# HMC830_PLL.net
KiCad netlist of a schematic drawn in Altium Designer
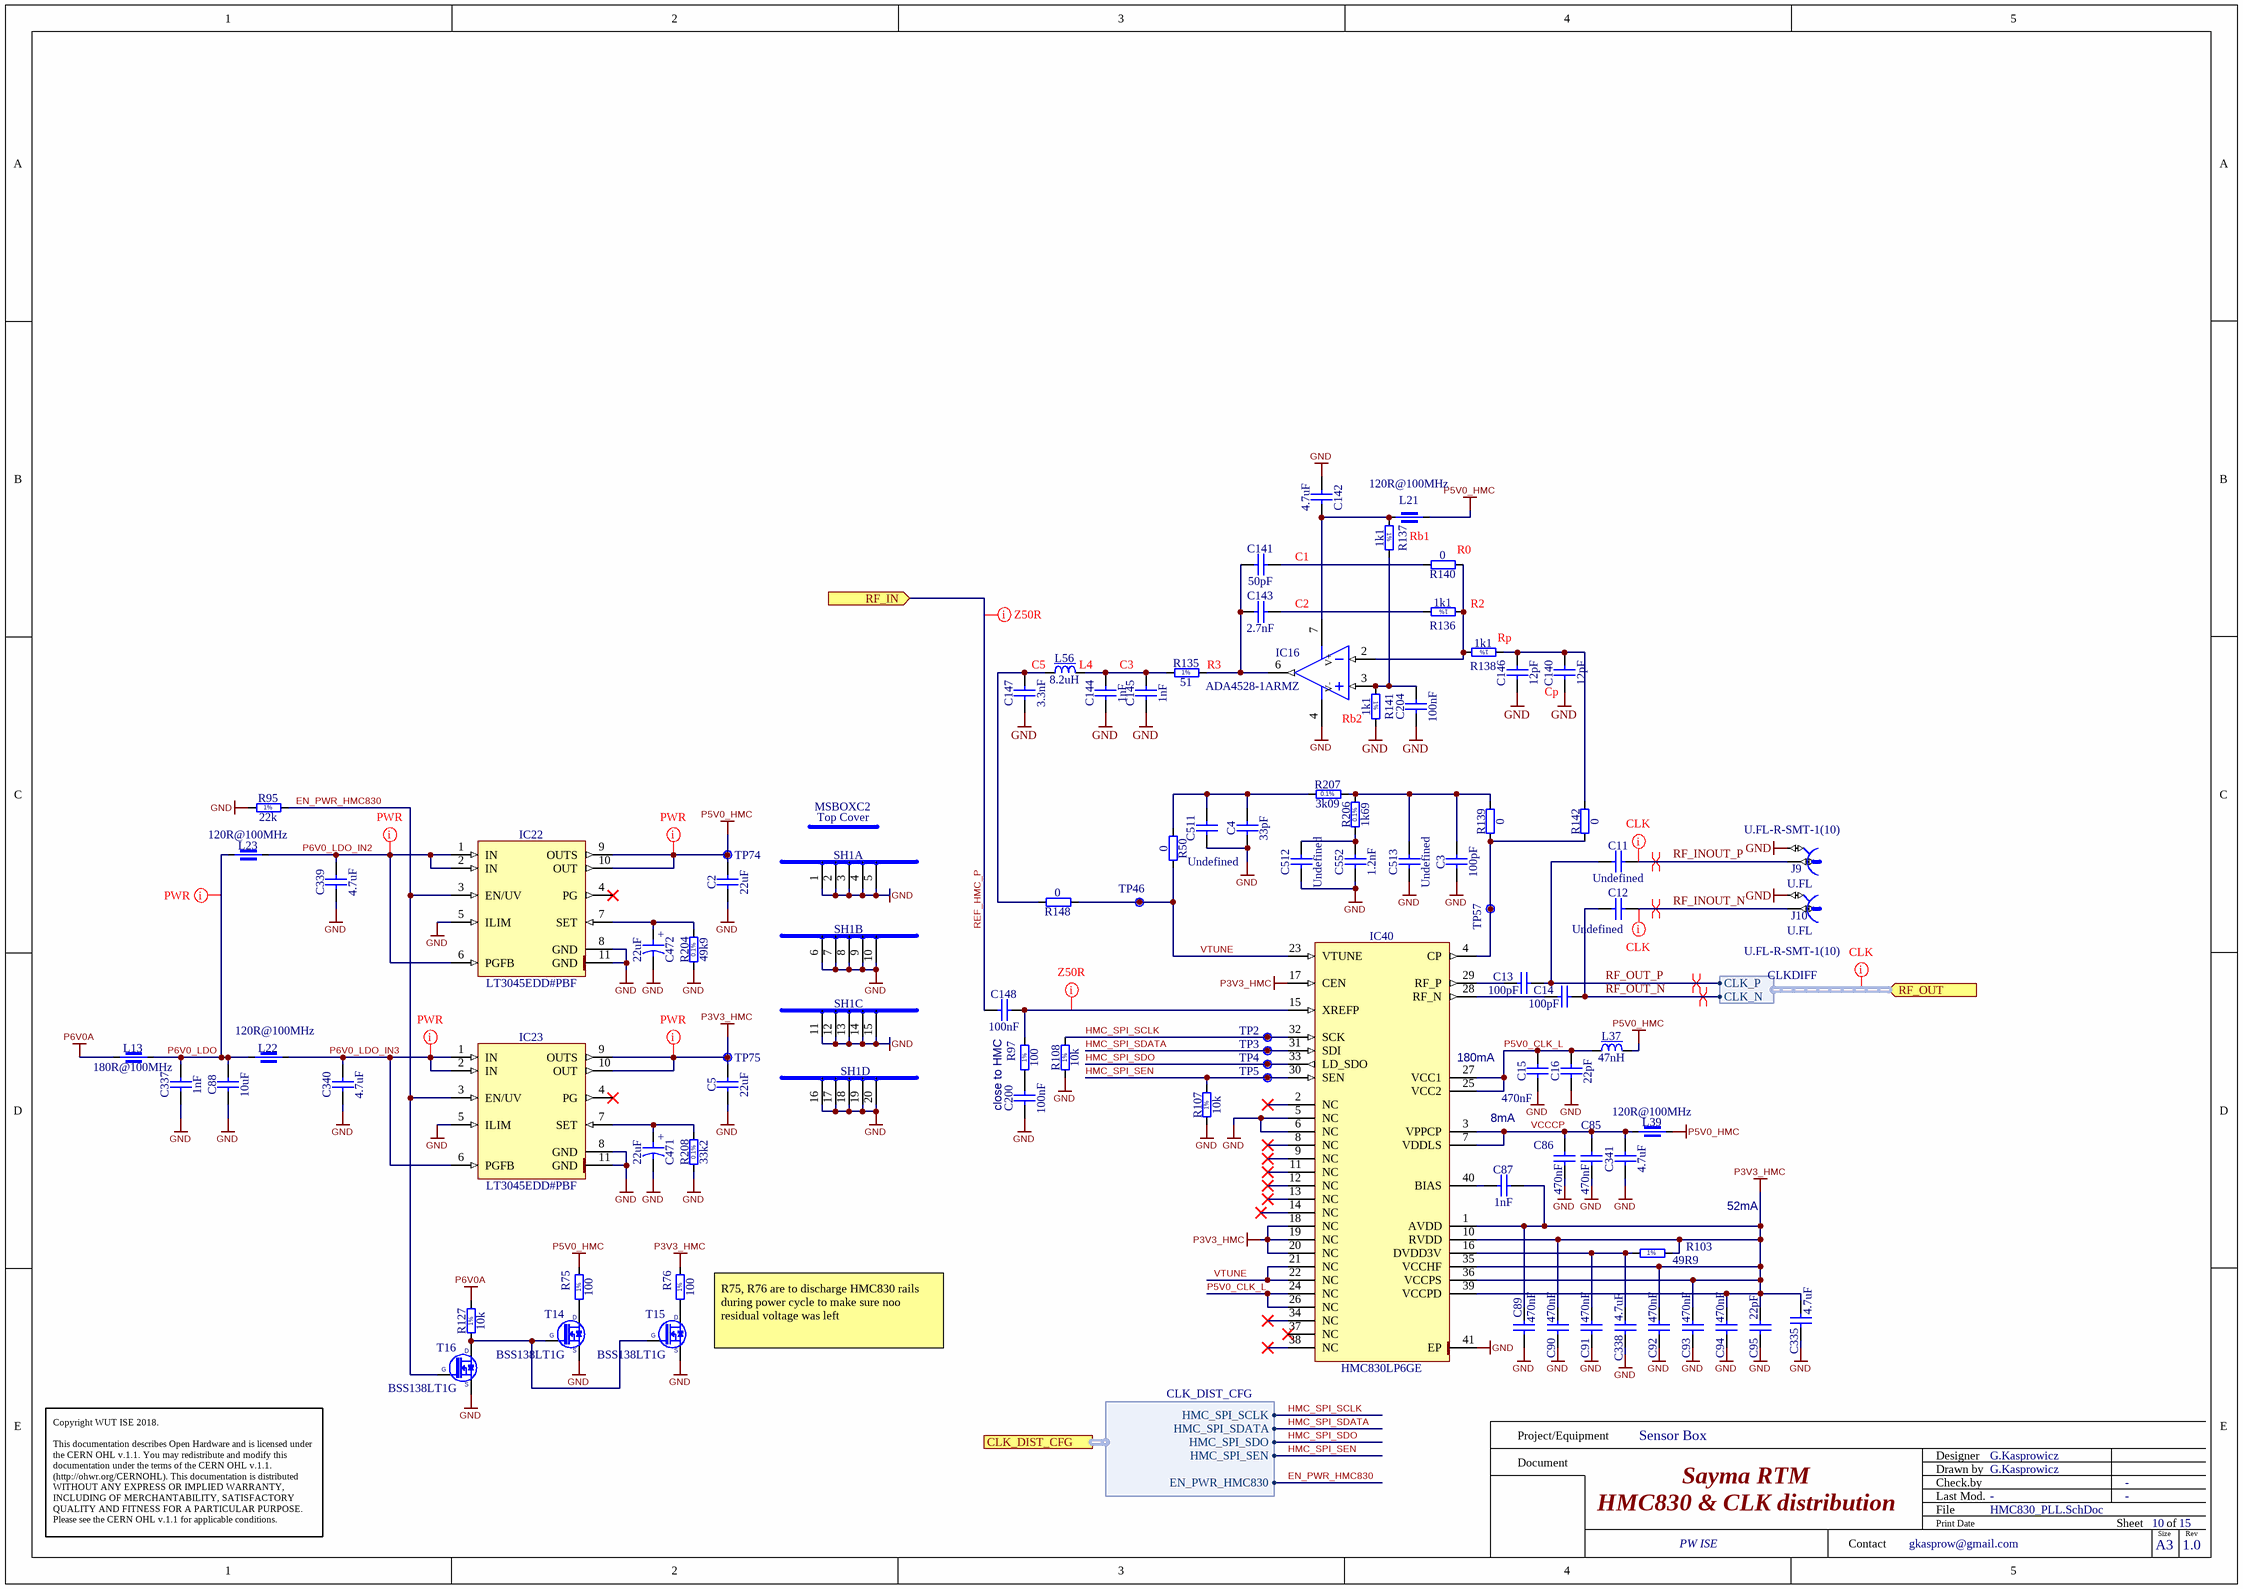
[diagram p0: HMC830_PLL.SchDoc]

(export (version "E")
  (design (tool "Eeschema 10.0.6"))
  (components
    (comp (ref "C2")
      (value "22uF")
      (footprint "CAPC2012X135N")
      (description "Non-polarised capacitor")
      (fields
        (field (name "MANUFACTURER PART NUMBER") "CC0805_22UF_16V_10%_X5R")
        (field (name "MANUFACTURER") "GENERIC")
      )
      (libsource (lib "Capacitors") (part "Capacitor - non polarized"))
    )
    (comp (ref "C3")
      (value "100pF")
      (footprint "CAPC1608X87N")
      (description "Non-polarised capacitor")
      (fields
        (field (name "MANUFACTURER PART NUMBER") "CC0603_100PF_50V_5%_NP0")
        (field (name "MANUFACTURER") "GENERIC")
      )
      (libsource (lib "Capacitors") (part "Capacitor - non polarized"))
    )
    (comp (ref "C4")
      (value "33pF")
      (footprint "CAPC1608X87N")
      (description "Non-polarised capacitor")
      (fields
        (field (name "MANUFACTURER PART NUMBER") "CC0603_33PF_50V_5%_NP0")
        (field (name "MANUFACTURER") "GENERIC")
      )
      (libsource (lib "Capacitors") (part "Capacitor - non polarized"))
    )
    (comp (ref "C5")
      (value "22uF")
      (footprint "CAPC2012X135N")
      (description "Non-polarised capacitor")
      (fields
        (field (name "MANUFACTURER PART NUMBER") "CC0805_22UF_16V_10%_X5R")
        (field (name "MANUFACTURER") "GENERIC")
      )
      (libsource (lib "Capacitors") (part "Capacitor - non polarized"))
    )
    (comp (ref "C11")
      (value "Undefined")
      (footprint "CAPC1005X55N")
      (description "Non-polarised capacitor")
      (fields (field (name "PART NUMBER") "CC0402_NO-VALUE"))
      (libsource (lib "Capacitors") (part "Capacitor - non polarized"))
    )
    (comp (ref "C12")
      (value "Undefined")
      (footprint "CAPC1005X55N")
      (description "Non-polarised capacitor")
      (fields (field (name "PART NUMBER") "CC0402_NO-VALUE"))
      (libsource (lib "Capacitors") (part "Capacitor - non polarized"))
    )
    (comp (ref "C13")
      (value "100pF")
      (footprint "CAPC1608X87N")
      (description "Non-polarised capacitor")
      (fields
        (field (name "MANUFACTURER PART NUMBER") "CC0603_100PF_50V_5%_NP0")
        (field (name "MANUFACTURER") "GENERIC")
      )
      (libsource (lib "Capacitors") (part "Capacitor - non polarized"))
    )
    (comp (ref "C14")
      (value "100pF")
      (footprint "CAPC1608X87N")
      (description "Non-polarised capacitor")
      (fields
        (field (name "MANUFACTURER PART NUMBER") "CC0603_100PF_50V_5%_NP0")
        (field (name "MANUFACTURER") "GENERIC")
      )
      (libsource (lib "Capacitors") (part "Capacitor - non polarized"))
    )
    (comp (ref "C15")
      (value "470nF")
      (footprint "CAPC1005X55N")
      (description "Non-polarised capacitor")
      (fields
        (field (name "MANUFACTURER PART NUMBER") "CC0402_470NF_16V_10%_X5R")
        (field (name "MANUFACTURER") "GENERIC")
      )
      (libsource (lib "Capacitors") (part "Capacitor - non polarized"))
    )
    (comp (ref "C16")
      (value "22pF")
      (footprint "CAPC1005X55N")
      (description "Non-polarised capacitor")
      (fields
        (field (name "MANUFACTURER PART NUMBER") "CC0402_22PF_50V_5%_C0G")
        (field (name "MANUFACTURER") "GENERIC")
      )
      (libsource (lib "Capacitors") (part "Capacitor - non polarized"))
    )
    (comp (ref "C85")
      (value "470nF")
      (footprint "CAPC1005X55N")
      (description "Non-polarised capacitor")
      (fields
        (field (name "MANUFACTURER PART NUMBER") "CC0402_470NF_16V_10%_X5R")
        (field (name "MANUFACTURER") "GENERIC")
      )
      (libsource (lib "Capacitors") (part "Capacitor - non polarized"))
    )
    (comp (ref "C86")
      (value "470nF")
      (footprint "CAPC1005X55N")
      (description "Non-polarised capacitor")
      (fields
        (field (name "MANUFACTURER PART NUMBER") "CC0402_470NF_16V_10%_X5R")
        (field (name "MANUFACTURER") "GENERIC")
      )
      (libsource (lib "Capacitors") (part "Capacitor - non polarized"))
    )
    (comp (ref "C87")
      (value "1nF")
      (footprint "CAPC1005X55N")
      (description "Non-polarised capacitor")
      (fields
        (field (name "MANUFACTURER PART NUMBER") "CC0402_1NF_50V_10%_X7R")
        (field (name "MANUFACTURER") "GENERIC")
      )
      (libsource (lib "Capacitors") (part "Capacitor - non polarized"))
    )
    (comp (ref "C88")
      (value "10uF")
      (footprint "CAPC3216X180N")
      (description "Non-polarised capacitor")
      (fields
        (field (name "MANUFACTURER PART NUMBER") "CC1206_10uF_25V_10%_X7R")
        (field (name "MANUFACTURER") "GENERIC")
      )
      (libsource (lib "Capacitors") (part "Capacitor - non polarized"))
    )
    (comp (ref "C89")
      (value "470nF")
      (footprint "CAPC1005X55N")
      (description "Non-polarised capacitor")
      (fields
        (field (name "MANUFACTURER PART NUMBER") "CC0402_470NF_16V_10%_X5R")
        (field (name "MANUFACTURER") "GENERIC")
      )
      (libsource (lib "Capacitors") (part "Capacitor - non polarized"))
    )
    (comp (ref "C90")
      (value "470nF")
      (footprint "CAPC1005X55N")
      (description "Non-polarised capacitor")
      (fields
        (field (name "MANUFACTURER PART NUMBER") "CC0402_470NF_16V_10%_X5R")
        (field (name "MANUFACTURER") "GENERIC")
      )
      (libsource (lib "Capacitors") (part "Capacitor - non polarized"))
    )
    (comp (ref "C91")
      (value "470nF")
      (footprint "CAPC1005X55N")
      (description "Non-polarised capacitor")
      (fields
        (field (name "MANUFACTURER PART NUMBER") "CC0402_470NF_16V_10%_X5R")
        (field (name "MANUFACTURER") "GENERIC")
      )
      (libsource (lib "Capacitors") (part "Capacitor - non polarized"))
    )
    (comp (ref "C92")
      (value "470nF")
      (footprint "CAPC1005X55N")
      (description "Non-polarised capacitor")
      (fields
        (field (name "MANUFACTURER PART NUMBER") "CC0402_470NF_16V_10%_X5R")
        (field (name "MANUFACTURER") "GENERIC")
      )
      (libsource (lib "Capacitors") (part "Capacitor - non polarized"))
    )
    (comp (ref "C93")
      (value "470nF")
      (footprint "CAPC1005X55N")
      (description "Non-polarised capacitor")
      (fields
        (field (name "MANUFACTURER PART NUMBER") "CC0402_470NF_16V_10%_X5R")
        (field (name "MANUFACTURER") "GENERIC")
      )
      (libsource (lib "Capacitors") (part "Capacitor - non polarized"))
    )
    (comp (ref "C94")
      (value "470nF")
      (footprint "CAPC1005X55N")
      (description "Non-polarised capacitor")
      (fields
        (field (name "MANUFACTURER PART NUMBER") "CC0402_470NF_16V_10%_X5R")
        (field (name "MANUFACTURER") "GENERIC")
      )
      (libsource (lib "Capacitors") (part "Capacitor - non polarized"))
    )
    (comp (ref "C95")
      (value "22pF")
      (footprint "CAPC1005X55N")
      (description "Non-polarised capacitor")
      (fields
        (field (name "MANUFACTURER PART NUMBER") "CC0402_22PF_50V_5%_C0G")
        (field (name "MANUFACTURER") "GENERIC")
      )
      (libsource (lib "Capacitors") (part "Capacitor - non polarized"))
    )
    (comp (ref "C140")
      (value "12pF")
      (footprint "CAPC1608X87N")
      (description "Non-polarised capacitor")
      (fields (field (name "PART NUMBER") "CC0603_12PF_50V_5%_NP0") (field (name "VOLTAGE") "50V"))
      (libsource (lib "Capacitors") (part "Capacitor - non polarized"))
    )
    (comp (ref "C141")
      (value "50pF")
      (footprint "CAPC1608X90N")
      (description "Non-polarised capacitor")
      (fields (field (name "PART NUMBER") "CC0603_50PF_50V_5%_NP0") (field (name "VOLTAGE") "50V"))
      (libsource (lib "Capacitors") (part "Capacitor - non polarized"))
    )
    (comp (ref "C142")
      (value "4.7uF")
      (footprint "CAPC1608X90N")
      (description "Non-polarised capacitor")
      (fields
        (field (name "MANUFACTURER PART NUMBER") "CC0603_4.7UF_25V_10%_X5R")
        (field (name "MANUFACTURER") "GENERIC")
      )
      (libsource (lib "Capacitors") (part "Capacitor - non polarized"))
    )
    (comp (ref "C143")
      (value "2.7nF")
      (footprint "CAPC3216X140N")
      (description "Non-polarised capacitor")
      (fields (field (name "PART NUMBER") "CC1206_2.7NF_100V_1%_NP0") (field (name "VOLTAGE") "100V"))
      (libsource (lib "Capacitors") (part "Capacitor - non polarized"))
    )
    (comp (ref "C144")
      (value "1nF")
      (footprint "CAPC1608X90N")
      (description "Non-polarised capacitor")
      (fields (field (name "PART NUMBER") "CC0603_1NF_50V_1%_NP0") (field (name "VOLTAGE") "50V"))
      (libsource (lib "Capacitors") (part "Capacitor - non polarized"))
    )
    (comp (ref "C145")
      (value "1nF")
      (footprint "CAPC1608X90N")
      (description "Non-polarised capacitor")
      (fields (field (name "PART NUMBER") "CC0603_1NF_50V_1%_NP0") (field (name "VOLTAGE") "50V"))
      (libsource (lib "Capacitors") (part "Capacitor - non polarized"))
    )
    (comp (ref "C146")
      (value "12pF")
      (footprint "CAPC1608X87N")
      (description "Non-polarised capacitor")
      (fields (field (name "PART NUMBER") "CC0603_12PF_50V_5%_NP0") (field (name "VOLTAGE") "50V"))
      (libsource (lib "Capacitors") (part "Capacitor - non polarized"))
    )
    (comp (ref "C147")
      (value "3.3nF")
      (footprint "CAPC1608X87N")
      (description "Non-polarised capacitor")
      (fields (field (name "PART NUMBER") "CC0603_3.3NF_50V_10%_X7R") (field (name "VOLTAGE") "50V"))
      (libsource (lib "Capacitors") (part "Capacitor - non polarized"))
    )
    (comp (ref "C148")
      (value "100nF")
      (footprint "CAPC0603X33N")
      (description "Non-polarised capacitor")
      (fields
        (field (name "MANUFACTURER PART NUMBER") "CC0201_100NF_6.3V_10%_X5R")
        (field (name "MANUFACTURER") "GENERIC")
      )
      (libsource (lib "Capacitors") (part "Capacitor - non polarized"))
    )
    (comp (ref "C200")
      (value "100nF")
      (footprint "CAPC0603X33N")
      (description "Non-polarised capacitor")
      (fields
        (field (name "MANUFACTURER PART NUMBER") "CC0201_100NF_6.3V_10%_X5R")
        (field (name "MANUFACTURER") "GENERIC")
      )
      (libsource (lib "Capacitors") (part "Capacitor - non polarized"))
    )
    (comp (ref "C204")
      (value "100nF")
      (footprint "CAPC0603X33N")
      (description "Non-polarised capacitor")
      (fields
        (field (name "MANUFACTURER PART NUMBER") "CC0201_100NF_6.3V_10%_X5R")
        (field (name "MANUFACTURER") "GENERIC")
      )
      (libsource (lib "Capacitors") (part "Capacitor - non polarized"))
    )
    (comp (ref "C335")
      (value "4.7uF")
      (footprint "CAPC1608X90N")
      (description "Non-polarised capacitor")
      (fields
        (field (name "MANUFACTURER PART NUMBER") "CC0603_4.7UF_25V_10%_X5R")
        (field (name "MANUFACTURER") "GENERIC")
      )
      (libsource (lib "Capacitors") (part "Capacitor - non polarized"))
    )
    (comp (ref "C337")
      (value "1nF")
      (footprint "CAPC1608X90N")
      (description "Non-polarised capacitor")
      (fields
        (field (name "MANUFACTURER PART NUMBER") "CC0603_1NF_50V_5%_NP0")
        (field (name "MANUFACTURER") "GENERIC")
      )
      (libsource (lib "Capacitors") (part "Capacitor - non polarized"))
    )
    (comp (ref "C338")
      (value "4.7uF")
      (footprint "CAPC1608X90N")
      (description "Non-polarised capacitor")
      (fields
        (field (name "MANUFACTURER PART NUMBER") "CC0603_4.7UF_25V_10%_X5R")
        (field (name "MANUFACTURER") "GENERIC")
      )
      (libsource (lib "Capacitors") (part "Capacitor - non polarized"))
    )
    (comp (ref "C339")
      (value "4.7uF")
      (footprint "CAPC1608X90N")
      (description "Non-polarised capacitor")
      (fields
        (field (name "MANUFACTURER PART NUMBER") "CC0603_4.7UF_25V_10%_X5R")
        (field (name "MANUFACTURER") "GENERIC")
      )
      (libsource (lib "Capacitors") (part "Capacitor - non polarized"))
    )
    (comp (ref "C340")
      (value "4.7uF")
      (footprint "CAPC1608X90N")
      (description "Non-polarised capacitor")
      (fields
        (field (name "MANUFACTURER PART NUMBER") "CC0603_4.7UF_25V_10%_X5R")
        (field (name "MANUFACTURER") "GENERIC")
      )
      (libsource (lib "Capacitors") (part "Capacitor - non polarized"))
    )
    (comp (ref "C341")
      (value "4.7uF")
      (footprint "CAPC1608X90N")
      (description "Non-polarised capacitor")
      (fields
        (field (name "MANUFACTURER PART NUMBER") "CC0603_4.7UF_25V_10%_X5R")
        (field (name "MANUFACTURER") "GENERIC")
      )
      (libsource (lib "Capacitors") (part "Capacitor - non polarized"))
    )
    (comp (ref "C471")
      (value "22uF")
      (footprint "CAPMP3216X180N")
      (description "Polarised capacitor")
      (fields
        (field (name "MANUFACTURER PART NUMBER") "CTE3216-18_22UF_6.3V_10%_LESR0900")
        (field (name "MANUFACTURER") "GENERIC")
      )
      (libsource (lib "Capacitors") (part "Capacitor - polarized"))
    )
    (comp (ref "C472")
      (value "22uF")
      (footprint "CAPMP3216X180N")
      (description "Polarised capacitor")
      (fields
        (field (name "MANUFACTURER PART NUMBER") "CTE3216-18_22UF_6.3V_10%_LESR0900")
        (field (name "MANUFACTURER") "GENERIC")
      )
      (libsource (lib "Capacitors") (part "Capacitor - polarized"))
    )
    (comp (ref "C511")
      (value "Undefined")
      (footprint "CAPC2012X135N")
      (description "Non-polarised capacitor")
      (fields (field (name "MANUFACTURER PART NUMBER") "CC0805_NO-VALUE"))
      (libsource (lib "Capacitors") (part "Capacitor - non polarized"))
    )
    (comp (ref "C512")
      (value "Undefined")
      (footprint "CAPC2012X135N")
      (description "Non-polarised capacitor")
      (fields (field (name "MANUFACTURER PART NUMBER") "CC0805_NO-VALUE"))
      (libsource (lib "Capacitors") (part "Capacitor - non polarized"))
    )
    (comp (ref "C513")
      (value "Undefined")
      (footprint "CAPC2012X135N")
      (description "Non-polarised capacitor")
      (fields (field (name "MANUFACTURER PART NUMBER") "CC0805_NO-VALUE"))
      (libsource (lib "Capacitors") (part "Capacitor - non polarized"))
    )
    (comp (ref "C552")
      (value "1.2nF")
      (footprint "CAPC3216X140N")
      (description "Non-polarised capacitor")
      (fields
        (field (name "MANUFACTURER PART NUMBER") "CC1206_1.2NF_50V_5%_NP0")
        (field (name "MANUFACTURER") "GENERIC")
      )
      (libsource (lib "Capacitors") (part "Capacitor - non polarized"))
    )
    (comp (ref "IC16")
      (value "ADA4528-1ARMZ")
      (footprint "SOP65P490X110-8N")
      (description "Operational Amplifier")
      (fields (field (name "MANUFACTURER") "ANALOG DEVICES"))
      (libsource (lib "ICs And Semiconductors") (part "Operational Amplifier Type1"))
    )
    (comp (ref "IC22")
      (value "LT3045EDD#PBF")
      (footprint "SON50P300X300X80-11N-R175X248")
      (description "20V, 500mA, Ultralow Noise, Ultrahigh PSRR Linear Regulator")
      (fields (field (name "MANUFACTURER") "LINEAR TECHNOLOGY"))
      (libsource (lib "ICs And Semiconductors") (part "LT3045EDD"))
    )
    (comp (ref "IC23")
      (value "LT3045EDD#PBF")
      (footprint "SON50P300X300X80-11N-R175X248")
      (description "20V, 500mA, Ultralow Noise, Ultrahigh PSRR Linear Regulator")
      (fields (field (name "MANUFACTURER") "LINEAR TECHNOLOGY"))
      (libsource (lib "ICs And Semiconductors") (part "LT3045EDD"))
    )
    (comp (ref "IC40")
      (value "HMC830LP6GE")
      (footprint "QFN50P600X600X90-41N-S475")
      (description "Fractional-N PLL With Integrated VCO, 25 to 3000MHz")
      (fields (field (name "MANUFACTURER") "HITTITE MICROWAVE CORP"))
      (libsource (lib "ICs And Semiconductors") (part "HMC830LP6GE"))
    )
    (comp (ref "J9")
      (value "U.FL")
      (footprint "HIROSE_U.FL-R-SMT-1(10)")
      (fields
        (field (name "FAMILY") "U.FL")
        (field (name "MANUFACTURER PART NUMBER") "U.FL-R-SMT-1(10)")
        (field (name "MANUFACTURER") "HIROSE (HRS)")
        (field (name "PART NUMBER") "HIROSE_U.FL-R-SMT-1(10)")
      )
      (libsource (lib "Connectors") (part "Coax_1Male_1Shield"))
    )
    (comp (ref "J10")
      (value "U.FL")
      (footprint "HIROSE_U.FL-R-SMT-1(10)")
      (fields
        (field (name "FAMILY") "U.FL")
        (field (name "MANUFACTURER PART NUMBER") "U.FL-R-SMT-1(10)")
        (field (name "MANUFACTURER") "HIROSE (HRS)")
        (field (name "PART NUMBER") "HIROSE_U.FL-R-SMT-1(10)")
      )
      (libsource (lib "Connectors") (part "Coax_1Male_1Shield"))
    )
    (comp (ref "L13")
      (value "180R@100MHz")
      (footprint "INDC4516X180N")
      (fields
        (field (name "MANUFACTURER PART NUMBER") "BLM41PG181SN1L")
        (field (name "MANUFACTURER") "MURATA")
        (field (name "PART NUMBER") "IND1806_MURATA_BLM41PG181SN1L")
      )
      (libsource (lib "Inductors & Transformers") (part "Ferrite Bead"))
    )
    (comp (ref "L21")
      (value "120R@100MHz")
      (footprint "INDC1608X95N")
      (fields
        (field (name "MANUFACTURER PART NUMBER") "BLM18PG121SN1D")
        (field (name "MANUFACTURER") "MURATA")
        (field (name "PART NUMBER") "IND0603_MURATA_BLM18PG121SN1D")
      )
      (libsource (lib "Inductors & Transformers") (part "Ferrite Bead"))
    )
    (comp (ref "L22")
      (value "120R@100MHz")
      (footprint "INDC1608X95N")
      (fields
        (field (name "MANUFACTURER PART NUMBER") "BLM18PG121SN1D")
        (field (name "MANUFACTURER") "MURATA")
        (field (name "PART NUMBER") "IND0603_MURATA_BLM18PG121SN1D")
      )
      (libsource (lib "Inductors & Transformers") (part "Ferrite Bead"))
    )
    (comp (ref "L23")
      (value "120R@100MHz")
      (footprint "INDC1608X95N")
      (fields
        (field (name "MANUFACTURER PART NUMBER") "BLM18PG121SN1D")
        (field (name "MANUFACTURER") "MURATA")
        (field (name "PART NUMBER") "IND0603_MURATA_BLM18PG121SN1D")
      )
      (libsource (lib "Inductors & Transformers") (part "Ferrite Bead"))
    )
    (comp (ref "L37")
      (value "47nH")
      (footprint "INDC2014X145N")
      (description "Inductor With Core")
      (fields (field (name "MANUFACTURER PART NUMBER") "B82498B3470J") (field (name "MANUFACTURER") "EPCOS"))
      (libsource (lib "Inductors & Transformers") (part "Inductor With Magnetic core"))
    )
    (comp (ref "L39")
      (value "120R@100MHz")
      (footprint "INDC1608X95N")
      (fields
        (field (name "MANUFACTURER PART NUMBER") "BLM18PG121SN1D")
        (field (name "MANUFACTURER") "MURATA")
        (field (name "PART NUMBER") "IND0603_MURATA_BLM18PG121SN1D")
      )
      (libsource (lib "Inductors & Transformers") (part "Ferrite Bead"))
    )
    (comp (ref "L56")
      (value "8.2uH")
      (footprint "IND_COILCRAFT_0603LS")
      (description "Inductor With Core")
      (fields (field (name "PART NUMBER") "IND_8.2UH_2%_COILCRAFT_0603LS") (field (name "POWER") "190mA"))
      (libsource (lib "LIBRARY_SCH") (part "L_0603_8.2uH"))
    )
    (comp (ref "MSBOXC2")
      (value "Top Cover")
      (footprint "MSBOX_WURTH_36003300")
      (description "Metal Screening Box - Top Cover 0 Pin")
      (fields (field (name "PART NUMBER") "MSBOX_WURTH_36003300") (field (name "MANUFACTURER") "WURTH"))
      (libsource (lib "Eletro-mechanical") (part "Metal Screening Box - Top Cover"))
    )
    (comp (ref "R50")
      (value "0")
      (footprint "RESC1608X55N")
      (description "Resistor")
      (fields (field (name "PART NUMBER") "R0603_0R_JUMPER") (field (name "MANUFACTURER") "GENERIC"))
      (libsource (lib "Resistors") (part "Resistor"))
    )
    (comp (ref "R75")
      (value "100")
      (footprint "RESC1005X40N")
      (description "Resistor - 1%")
      (fields
        (field (name "MANUFACTURER PART NUMBER") "R0402_100R_1%_0.0625W_100PPM")
        (field (name "MANUFACTURER") "GENERIC")
      )
      (libsource (lib "Resistors") (part "Resistor - 1%"))
    )
    (comp (ref "R76")
      (value "100")
      (footprint "RESC1005X40N")
      (description "Resistor - 1%")
      (fields
        (field (name "MANUFACTURER PART NUMBER") "R0402_100R_1%_0.0625W_100PPM")
        (field (name "MANUFACTURER") "GENERIC")
      )
      (libsource (lib "Resistors") (part "Resistor - 1%"))
    )
    (comp (ref "R95")
      (value "22k")
      (footprint "RESC1005X40N")
      (description "Resistor - 1%")
      (fields
        (field (name "MANUFACTURER PART NUMBER") "R0402_22K_1%_0.0625W_100PPM")
        (field (name "MANUFACTURER") "GENERIC")
      )
      (libsource (lib "Resistors") (part "Resistor - 1%"))
    )
    (comp (ref "R97")
      (value "100")
      (footprint "RESC1005X40N")
      (description "Resistor - 1%")
      (fields
        (field (name "MANUFACTURER PART NUMBER") "R0402_100R_1%_0.0625W_100PPM")
        (field (name "MANUFACTURER") "GENERIC")
      )
      (libsource (lib "Resistors") (part "Resistor - 1%"))
    )
    (comp (ref "R103")
      (value "49R9")
      (footprint "RESC1005X40N")
      (description "Resistor - 1%")
      (fields
        (field (name "MANUFACTURER PART NUMBER") "R0402_49R9_1%_0.0625W_100PPM")
        (field (name "MANUFACTURER") "GENERIC")
      )
      (libsource (lib "Resistors") (part "Resistor - 1%"))
    )
    (comp (ref "R107")
      (value "10k")
      (footprint "RESC1005X40N")
      (description "Resistor - 1%")
      (fields
        (field (name "MANUFACTURER PART NUMBER") "R0402_10K_1%_0.0625W_100PPM")
        (field (name "MANUFACTURER") "GENERIC")
      )
      (libsource (lib "Resistors") (part "Resistor - 1%"))
    )
    (comp (ref "R108")
      (value "10k")
      (footprint "RESC1005X40N")
      (description "Resistor - 1%")
      (fields
        (field (name "MANUFACTURER PART NUMBER") "R0402_10K_1%_0.0625W_100PPM")
        (field (name "MANUFACTURER") "GENERIC")
      )
      (libsource (lib "Resistors") (part "Resistor - 1%"))
    )
    (comp (ref "R127")
      (value "10k")
      (footprint "RESC1005X40N")
      (description "Resistor - 1%")
      (fields
        (field (name "MANUFACTURER PART NUMBER") "R0402_10K_1%_0.0625W_100PPM")
        (field (name "MANUFACTURER") "GENERIC")
      )
      (libsource (lib "Resistors") (part "Resistor - 1%"))
    )
    (comp (ref "R135")
      (value "51")
      (footprint "RESC1608X55N")
      (description "Resistor - 1%")
      (fields (field (name "PART NUMBER") "R0603_51R_1%_0.1W_100PPM") (field (name "POWER") "0.1W"))
      (libsource (lib "Resistors") (part "Resistor - 1%"))
    )
    (comp (ref "R136")
      (value "1k1")
      (footprint "RESC1608X55N")
      (description "Resistor - 1%")
      (fields (field (name "PART NUMBER") "R0603_1K1_1%_0.1W_100PPM") (field (name "POWER") "0.1W"))
      (libsource (lib "Resistors") (part "Resistor - 1%"))
    )
    (comp (ref "R137")
      (value "1k1")
      (footprint "RESC1608X55N")
      (description "Resistor - 1%")
      (fields (field (name "PART NUMBER") "R0603_1K1_1%_0.1W_100PPM") (field (name "POWER") "0.1W"))
      (libsource (lib "Resistors") (part "Resistor - 1%"))
    )
    (comp (ref "R138")
      (value "1k1")
      (footprint "RESC1608X55N")
      (description "Resistor - 1%")
      (fields (field (name "PART NUMBER") "R0603_1K1_1%_0.1W_100PPM") (field (name "POWER") "0.1W"))
      (libsource (lib "Resistors") (part "Resistor - 1%"))
    )
    (comp (ref "R139")
      (value "0")
      (footprint "RESC1608X55N")
      (description "Resistor")
      (fields (field (name "PART NUMBER") "R0603_0R_JUMPER") (field (name "MANUFACTURER") "GENERIC"))
      (libsource (lib "Resistors") (part "Resistor"))
    )
    (comp (ref "R140")
      (value "0")
      (footprint "RESC1608X55N")
      (description "Resistor")
      (fields (field (name "PART NUMBER") "R0603_0R_JUMPER") (field (name "MANUFACTURER") "GENERIC"))
      (libsource (lib "Resistors") (part "Resistor"))
    )
    (comp (ref "R141")
      (value "1k1")
      (footprint "RESC1608X55N")
      (description "Resistor - 1%")
      (fields (field (name "PART NUMBER") "R0603_1K1_1%_0.1W_100PPM") (field (name "POWER") "0.1W"))
      (libsource (lib "Resistors") (part "Resistor - 1%"))
    )
    (comp (ref "R142")
      (value "0")
      (footprint "RESC1608X55N")
      (description "Resistor")
      (fields (field (name "PART NUMBER") "R0603_0R_JUMPER") (field (name "MANUFACTURER") "GENERIC"))
      (libsource (lib "Resistors") (part "Resistor"))
    )
    (comp (ref "R148")
      (value "0")
      (footprint "RESC1608X55N")
      (description "Resistor")
      (fields (field (name "PART NUMBER") "R0603_0R_JUMPER") (field (name "MANUFACTURER") "GENERIC"))
      (libsource (lib "Resistors") (part "Resistor"))
    )
    (comp (ref "R204")
      (value "49k9")
      (footprint "RESC1608X55N")
      (description "Resistor - 0.1%")
      (fields
        (field (name "MANUFACTURER PART NUMBER") "R0603_49K9_0.1%_0.063W_10PPM")
        (field (name "MANUFACTURER") "GENERIC")
      )
      (libsource (lib "Resistors") (part "Resistor - 0.1%"))
    )
    (comp (ref "R206")
      (value "1k69")
      (footprint "RESC1608X55N")
      (description "Resistor - 0.1%")
      (fields
        (field (name "MANUFACTURER PART NUMBER") "R0603_1K69_0.1%_0.063W_10PPM")
        (field (name "MANUFACTURER") "GENERIC")
      )
      (libsource (lib "Resistors") (part "Resistor - 0.1%"))
    )
    (comp (ref "R207")
      (value "3k09")
      (footprint "RESC1608X55N")
      (description "Resistor - 0.1%")
      (fields
        (field (name "MANUFACTURER PART NUMBER") "R0603_3K09_0.1%_0.063W_10PPM")
        (field (name "MANUFACTURER") "GENERIC")
      )
      (libsource (lib "Resistors") (part "Resistor - 0.1%"))
    )
    (comp (ref "R208")
      (value "33k2")
      (footprint "RESC1608X55N")
      (description "Resistor - 0.1%")
      (fields
        (field (name "MANUFACTURER PART NUMBER") "R0603_33K2_0.1%_0.063W_10PPM")
        (field (name "MANUFACTURER") "GENERIC")
      )
      (libsource (lib "Resistors") (part "Resistor - 0.1%"))
    )
    (comp (ref "SH1")
      (value "Metal Screening Box 4x5 Pins")
      (footprint "MSBOX_WURTH_36103305")
      (description "Metal Screening Box 20 (4x5) Pins")
      (fields (field (name "MANUFACTURER PART NUMBER") "36103305") (field (name "MANUFACTURER") "WURTH"))
      (libsource (lib "Eletro-mechanical") (part "Metal Screening Box - 4x5 pins"))
    )
    (comp (ref "T14")
      (value "BSS138LT1G")
      (footprint "SOT95P240X110-3N")
      (description "N-CHANNEL MOSFET WITH DIODE")
      (fields (field (name "MANUFACTURER") "ON SEMICONDUCTOR"))
      (libsource (lib "ICs And Semiconductors") (part "N-MOSFET-D 1G 2S 3D"))
    )
    (comp (ref "T15")
      (value "BSS138LT1G")
      (footprint "SOT95P240X110-3N")
      (description "N-CHANNEL MOSFET WITH DIODE")
      (fields (field (name "MANUFACTURER") "ON SEMICONDUCTOR"))
      (libsource (lib "ICs And Semiconductors") (part "N-MOSFET-D 1G 2S 3D"))
    )
    (comp (ref "T16")
      (value "BSS138LT1G")
      (footprint "SOT95P240X110-3N")
      (description "N-CHANNEL MOSFET WITH DIODE")
      (fields (field (name "MANUFACTURER") "ON SEMICONDUCTOR"))
      (libsource (lib "ICs And Semiconductors") (part "N-MOSFET-D 1G 2S 3D"))
    )
    (comp (ref "TP2")
      (value "Test Point")
      (footprint "TPS127")
      (fields (field (name "PART NUMBER") "SMD_PAD_1.27X1.27MM"))
      (libsource (lib "Eletro-mechanical") (part "Test Point"))
    )
    (comp (ref "TP3")
      (value "Test Point")
      (footprint "TPS127")
      (fields (field (name "PART NUMBER") "SMD_PAD_1.27X1.27MM"))
      (libsource (lib "Eletro-mechanical") (part "Test Point"))
    )
    (comp (ref "TP4")
      (value "Test Point")
      (footprint "TPS127")
      (fields (field (name "PART NUMBER") "SMD_PAD_1.27X1.27MM"))
      (libsource (lib "Eletro-mechanical") (part "Test Point"))
    )
    (comp (ref "TP5")
      (value "Test Point")
      (footprint "TPS127")
      (fields (field (name "PART NUMBER") "SMD_PAD_1.27X1.27MM"))
      (libsource (lib "Eletro-mechanical") (part "Test Point"))
    )
    (comp (ref "TP46")
      (value "Test Point")
      (footprint "TPS127")
      (fields (field (name "PART NUMBER") "SMD_PAD_1.27X1.27MM"))
      (libsource (lib "Eletro-mechanical") (part "Test Point"))
    )
    (comp (ref "TP57")
      (value "Test Point")
      (footprint "TPS127")
      (fields (field (name "PART NUMBER") "SMD_PAD_1.27X1.27MM"))
      (libsource (lib "Eletro-mechanical") (part "Test Point"))
    )
    (comp (ref "TP74")
      (value "Test Point")
      (footprint "TPS127")
      (fields (field (name "PART NUMBER") "SMD_PAD_1.27X1.27MM"))
      (libsource (lib "Eletro-mechanical") (part "Test Point"))
    )
    (comp (ref "TP75")
      (value "Test Point")
      (footprint "TPS127")
      (fields (field (name "PART NUMBER") "SMD_PAD_1.27X1.27MM"))
      (libsource (lib "Eletro-mechanical") (part "Test Point"))
    )
  )
  (nets
    (net (code "3") (name "/EN_PWR_HMC830") (class "Default")
      (node (ref "IC22") (pin "3") (pinfunction "EN/UV_3") (pintype "input"))
      (node (ref "IC23") (pin "3") (pinfunction "EN/UV_3") (pintype "input"))
      (node (ref "R95") (pin "2") (pinfunction "2_2") (pintype "passive"))
      (node (ref "T16") (pin "1") (pinfunction "G_1") (pintype "passive"))
    )
    (net (code "4") (name "/HMC_SPI_SCLK") (class "Default")
      (node (ref "IC40") (pin "32") (pinfunction "SCK_32") (pintype "input"))
      (node (ref "R108") (pin "2") (pinfunction "2_2") (pintype "passive"))
      (node (ref "TP2") (pin "1") (pinfunction "1_1") (pintype "bidirectional"))
    )
    (net (code "5") (name "/HMC_SPI_SDATA") (class "Default")
      (node (ref "IC40") (pin "31") (pinfunction "SDI_31") (pintype "input"))
      (node (ref "TP3") (pin "1") (pinfunction "1_1") (pintype "bidirectional"))
    )
    (net (code "6") (name "/HMC_SPI_SDO") (class "Default")
      (node (ref "IC40") (pin "33") (pinfunction "LD_SDO_33") (pintype "output"))
      (node (ref "TP4") (pin "1") (pinfunction "1_1") (pintype "bidirectional"))
    )
    (net (code "7") (name "/HMC_SPI_SEN") (class "Default")
      (node (ref "IC40") (pin "30") (pinfunction "SEN_30") (pintype "input"))
      (node (ref "R107") (pin "2") (pinfunction "2_2") (pintype "passive"))
      (node (ref "TP5") (pin "1") (pinfunction "1_1") (pintype "bidirectional"))
    )
    (net (code "8") (name "/P5V0_CLK_L") (class "Default")
      (node (ref "C15") (pin "2") (pinfunction "2_2") (pintype "passive"))
      (node (ref "C16") (pin "2") (pinfunction "2_2") (pintype "passive"))
      (node (ref "IC40") (pin "24") (pinfunction "NC_24") (pintype "passive"))
      (node (ref "IC40") (pin "25") (pinfunction "VCC2_25") (pintype "power_in"))
      (node (ref "IC40") (pin "26") (pinfunction "NC_26") (pintype "passive"))
      (node (ref "IC40") (pin "27") (pinfunction "VCC1_27") (pintype "power_in"))
      (node (ref "L37") (pin "1") (pinfunction "1_1") (pintype "passive"))
    )
    (net (code "9") (name "/P6V0_LDO") (class "Default")
      (node (ref "C337") (pin "2") (pinfunction "2_2") (pintype "passive"))
      (node (ref "C88") (pin "2") (pinfunction "2_2") (pintype "passive"))
      (node (ref "L13") (pin "2") (pinfunction "2_2") (pintype "passive"))
      (node (ref "L22") (pin "1") (pinfunction "1_1") (pintype "passive"))
      (node (ref "L23") (pin "1") (pinfunction "1_1") (pintype "passive"))
    )
    (net (code "10") (name "/P6V0_LDO_IN2") (class "Default")
      (node (ref "C339") (pin "2") (pinfunction "2_2") (pintype "passive"))
      (node (ref "IC22") (pin "1") (pinfunction "IN_1") (pintype "input"))
      (node (ref "IC22") (pin "2") (pinfunction "IN_2") (pintype "input"))
      (node (ref "IC22") (pin "6") (pinfunction "PGFB_6") (pintype "input"))
      (node (ref "L23") (pin "2") (pinfunction "2_2") (pintype "passive"))
    )
    (net (code "11") (name "/P6V0_LDO_IN3") (class "Default")
      (node (ref "C340") (pin "2") (pinfunction "2_2") (pintype "passive"))
      (node (ref "IC23") (pin "1") (pinfunction "IN_1") (pintype "input"))
      (node (ref "IC23") (pin "2") (pinfunction "IN_2") (pintype "input"))
      (node (ref "IC23") (pin "6") (pinfunction "PGFB_6") (pintype "input"))
      (node (ref "L22") (pin "2") (pinfunction "2_2") (pintype "passive"))
    )
    (net (code "12") (name "/REF_HMC_P") (class "Default")
      (node (ref "C148") (pin "1") (pinfunction "1_1") (pintype "passive"))
    )
    (net (code "13") (name "/RF_INOUT_N") (class "Default")
      (node (ref "C12") (pin "2") (pinfunction "2_2") (pintype "passive"))
      (node (ref "J10") (pin "1") (pinfunction "1_1") (pintype "bidirectional"))
    )
    (net (code "14") (name "/RF_INOUT_P") (class "Default")
      (node (ref "C11") (pin "2") (pinfunction "2_2") (pintype "passive"))
      (node (ref "J9") (pin "1") (pinfunction "1_1") (pintype "bidirectional"))
    )
    (net (code "15") (name "/RF_OUT_N") (class "Default")
      (node (ref "C12") (pin "1") (pinfunction "1_1") (pintype "passive"))
      (node (ref "C14") (pin "1") (pinfunction "1_1") (pintype "passive"))
    )
    (net (code "16") (name "/RF_OUT_P") (class "Default")
      (node (ref "C11") (pin "1") (pinfunction "1_1") (pintype "passive"))
      (node (ref "C13") (pin "1") (pinfunction "1_1") (pintype "passive"))
    )
    (net (code "17") (name "/VCCCP") (class "Default")
      (node (ref "C341") (pin "2") (pinfunction "2_2") (pintype "passive"))
      (node (ref "C85") (pin "2") (pinfunction "2_2") (pintype "passive"))
      (node (ref "C86") (pin "2") (pinfunction "2_2") (pintype "passive"))
      (node (ref "IC40") (pin "3") (pinfunction "VPPCP_3") (pintype "power_in"))
      (node (ref "IC40") (pin "7") (pinfunction "VDDLS_7") (pintype "power_in"))
      (node (ref "L39") (pin "1") (pinfunction "1_1") (pintype "passive"))
    )
    (net (code "18") (name "/VTUNE") (class "Default")
      (node (ref "IC40") (pin "21") (pinfunction "NC_21") (pintype "passive"))
      (node (ref "IC40") (pin "22") (pinfunction "NC_22") (pintype "passive"))
      (node (ref "IC40") (pin "23") (pinfunction "VTUNE_23") (pintype "input"))
      (node (ref "R148") (pin "1") (pinfunction "1_1") (pintype "passive"))
      (node (ref "R50") (pin "2") (pinfunction "2_2") (pintype "passive"))
      (node (ref "TP46") (pin "1") (pinfunction "1_1") (pintype "bidirectional"))
    )
    (net (code "21") (name "GND") (class "Default")
      (node (ref "C140") (pin "1") (pinfunction "1_1") (pintype "passive"))
      (node (ref "C142") (pin "1") (pinfunction "1_1") (pintype "passive"))
      (node (ref "C144") (pin "1") (pinfunction "1_1") (pintype "passive"))
      (node (ref "C145") (pin "1") (pinfunction "1_1") (pintype "passive"))
      (node (ref "C146") (pin "1") (pinfunction "1_1") (pintype "passive"))
      (node (ref "C147") (pin "1") (pinfunction "1_1") (pintype "passive"))
      (node (ref "C15") (pin "1") (pinfunction "1_1") (pintype "passive"))
      (node (ref "C16") (pin "1") (pinfunction "1_1") (pintype "passive"))
      (node (ref "C2") (pin "1") (pinfunction "1_1") (pintype "passive"))
      (node (ref "C200") (pin "1") (pinfunction "1_1") (pintype "passive"))
      (node (ref "C204") (pin "1") (pinfunction "1_1") (pintype "passive"))
      (node (ref "C3") (pin "1") (pinfunction "1_1") (pintype "passive"))
      (node (ref "C335") (pin "1") (pinfunction "1_1") (pintype "passive"))
      (node (ref "C337") (pin "1") (pinfunction "1_1") (pintype "passive"))
      (node (ref "C338") (pin "1") (pinfunction "1_1") (pintype "passive"))
      (node (ref "C339") (pin "1") (pinfunction "1_1") (pintype "passive"))
      (node (ref "C340") (pin "1") (pinfunction "1_1") (pintype "passive"))
      (node (ref "C341") (pin "1") (pinfunction "1_1") (pintype "passive"))
      (node (ref "C4") (pin "1") (pinfunction "1_1") (pintype "passive"))
      (node (ref "C471") (pin "2") (pinfunction "2_2") (pintype "passive"))
      (node (ref "C472") (pin "2") (pinfunction "2_2") (pintype "passive"))
      (node (ref "C5") (pin "1") (pinfunction "1_1") (pintype "passive"))
      (node (ref "C511") (pin "1") (pinfunction "1_1") (pintype "passive"))
      (node (ref "C512") (pin "1") (pinfunction "1_1") (pintype "passive"))
      (node (ref "C513") (pin "1") (pinfunction "1_1") (pintype "passive"))
      (node (ref "C552") (pin "1") (pinfunction "1_1") (pintype "passive"))
      (node (ref "C85") (pin "1") (pinfunction "1_1") (pintype "passive"))
      (node (ref "C86") (pin "1") (pinfunction "1_1") (pintype "passive"))
      (node (ref "C88") (pin "1") (pinfunction "1_1") (pintype "passive"))
      (node (ref "C89") (pin "1") (pinfunction "1_1") (pintype "passive"))
      (node (ref "C90") (pin "1") (pinfunction "1_1") (pintype "passive"))
      (node (ref "C91") (pin "1") (pinfunction "1_1") (pintype "passive"))
      (node (ref "C92") (pin "1") (pinfunction "1_1") (pintype "passive"))
      (node (ref "C93") (pin "1") (pinfunction "1_1") (pintype "passive"))
      (node (ref "C94") (pin "1") (pinfunction "1_1") (pintype "passive"))
      (node (ref "C95") (pin "1") (pinfunction "1_1") (pintype "passive"))
      (node (ref "IC16") (pin "4") (pinfunction "V-_4") (pintype "power_in"))
      (node (ref "IC22") (pin "11") (pinfunction "GND_11") (pintype "power_in"))
      (node (ref "IC22") (pin "5") (pinfunction "ILIM_5") (pintype "input"))
      (node (ref "IC22") (pin "8") (pinfunction "GND_8") (pintype "power_in"))
      (node (ref "IC23") (pin "11") (pinfunction "GND_11") (pintype "power_in"))
      (node (ref "IC23") (pin "5") (pinfunction "ILIM_5") (pintype "input"))
      (node (ref "IC23") (pin "8") (pinfunction "GND_8") (pintype "power_in"))
      (node (ref "IC40") (pin "41") (pinfunction "EP_41") (pintype "power_in"))
      (node (ref "IC40") (pin "5") (pinfunction "NC_5") (pintype "passive"))
      (node (ref "IC40") (pin "6") (pinfunction "NC_6") (pintype "passive"))
      (node (ref "J10") (pin "2") (pinfunction "2_2") (pintype "bidirectional"))
      (node (ref "J9") (pin "2") (pinfunction "2_2") (pintype "bidirectional"))
      (node (ref "R107") (pin "1") (pinfunction "1_1") (pintype "passive"))
      (node (ref "R108") (pin "1") (pinfunction "1_1") (pintype "passive"))
      (node (ref "R141") (pin "2") (pinfunction "2_2") (pintype "passive"))
      (node (ref "R204") (pin "1") (pinfunction "1_1") (pintype "passive"))
      (node (ref "R208") (pin "1") (pinfunction "1_1") (pintype "passive"))
      (node (ref "R95") (pin "1") (pinfunction "1_1") (pintype "passive"))
      (node (ref "SH1") (pin "1") (pinfunction "1_1") (pintype "passive"))
      (node (ref "SH1") (pin "10") (pinfunction "10_10") (pintype "passive"))
      (node (ref "SH1") (pin "11") (pinfunction "11_11") (pintype "passive"))
      (node (ref "SH1") (pin "12") (pinfunction "12_12") (pintype "passive"))
      (node (ref "SH1") (pin "13") (pinfunction "13_13") (pintype "passive"))
      (node (ref "SH1") (pin "14") (pinfunction "14_14") (pintype "passive"))
      (node (ref "SH1") (pin "15") (pinfunction "15_15") (pintype "passive"))
      (node (ref "SH1") (pin "16") (pinfunction "16_16") (pintype "passive"))
      (node (ref "SH1") (pin "17") (pinfunction "17_17") (pintype "passive"))
      (node (ref "SH1") (pin "18") (pinfunction "18_18") (pintype "passive"))
      (node (ref "SH1") (pin "19") (pinfunction "19_19") (pintype "passive"))
      (node (ref "SH1") (pin "2") (pinfunction "2_2") (pintype "passive"))
      (node (ref "SH1") (pin "20") (pinfunction "20_20") (pintype "passive"))
      (node (ref "SH1") (pin "3") (pinfunction "3_3") (pintype "passive"))
      (node (ref "SH1") (pin "4") (pinfunction "4_4") (pintype "passive"))
      (node (ref "SH1") (pin "5") (pinfunction "5_5") (pintype "passive"))
      (node (ref "SH1") (pin "6") (pinfunction "6_6") (pintype "passive"))
      (node (ref "SH1") (pin "7") (pinfunction "7_7") (pintype "passive"))
      (node (ref "SH1") (pin "8") (pinfunction "8_8") (pintype "passive"))
      (node (ref "SH1") (pin "9") (pinfunction "9_9") (pintype "passive"))
      (node (ref "T14") (pin "2") (pinfunction "S_2") (pintype "passive"))
      (node (ref "T15") (pin "2") (pinfunction "S_2") (pintype "passive"))
      (node (ref "T16") (pin "2") (pinfunction "S_2") (pintype "passive"))
    )
    (net (code "22") (name "Net-(C3-Pad2)") (class "Default")
      (node (ref "C3") (pin "2") (pinfunction "2_2") (pintype "passive"))
      (node (ref "C513") (pin "2") (pinfunction "2_2") (pintype "passive"))
      (node (ref "R139") (pin "2") (pinfunction "2_2") (pintype "passive"))
      (node (ref "R206") (pin "2") (pinfunction "2_2") (pintype "passive"))
      (node (ref "R207") (pin "2") (pinfunction "2_2") (pintype "passive"))
    )
    (net (code "23") (name "Net-(C4-Pad2)") (class "Default")
      (node (ref "C4") (pin "2") (pinfunction "2_2") (pintype "passive"))
      (node (ref "C511") (pin "2") (pinfunction "2_2") (pintype "passive"))
      (node (ref "R207") (pin "1") (pinfunction "1_1") (pintype "passive"))
      (node (ref "R50") (pin "1") (pinfunction "1_1") (pintype "passive"))
    )
    (net (code "24") (name "Net-(C140-Pad2)") (class "Default")
      (node (ref "C140") (pin "2") (pinfunction "2_2") (pintype "passive"))
      (node (ref "C146") (pin "2") (pinfunction "2_2") (pintype "passive"))
      (node (ref "R138") (pin "1") (pinfunction "1_1") (pintype "passive"))
      (node (ref "R142") (pin "2") (pinfunction "2_2") (pintype "passive"))
    )
    (net (code "25") (name "Net-(C141-Pad2)") (class "Default")
      (node (ref "C141") (pin "2") (pinfunction "2_2") (pintype "passive"))
      (node (ref "R140") (pin "2") (pinfunction "2_2") (pintype "passive"))
    )
    (net (code "26") (name "Net-(C143-Pad2)") (class "Default")
      (node (ref "C143") (pin "2") (pinfunction "2_2") (pintype "passive"))
      (node (ref "R136") (pin "2") (pinfunction "2_2") (pintype "passive"))
    )
    (net (code "27") (name "Net-(C144-Pad2)") (class "Default")
      (node (ref "C144") (pin "2") (pinfunction "2_2") (pintype "passive"))
      (node (ref "C145") (pin "2") (pinfunction "2_2") (pintype "passive"))
      (node (ref "L56") (pin "2") (pinfunction "2_2") (pintype "passive"))
      (node (ref "R135") (pin "1") (pinfunction "1_1") (pintype "passive"))
    )
    (net (code "28") (name "Net-(C147-Pad2)") (class "Default")
      (node (ref "C147") (pin "2") (pinfunction "2_2") (pintype "passive"))
      (node (ref "L56") (pin "1") (pinfunction "1_1") (pintype "passive"))
      (node (ref "R148") (pin "2") (pinfunction "2_2") (pintype "passive"))
    )
    (net (code "29") (name "Net-(C200-Pad2)") (class "Default")
      (node (ref "C200") (pin "2") (pinfunction "2_2") (pintype "passive"))
      (node (ref "R97") (pin "1") (pinfunction "1_1") (pintype "passive"))
    )
    (net (code "30") (name "Net-(C512-Pad2)") (class "Default")
      (node (ref "C512") (pin "2") (pinfunction "2_2") (pintype "passive"))
      (node (ref "C552") (pin "2") (pinfunction "2_2") (pintype "passive"))
      (node (ref "R206") (pin "1") (pinfunction "1_1") (pintype "passive"))
    )
    (net (code "31") (name "Net-(IC16-IN+)") (class "Default")
      (node (ref "C204") (pin "2") (pinfunction "2_2") (pintype "passive"))
      (node (ref "IC16") (pin "3") (pinfunction "IN+_3") (pintype "input"))
      (node (ref "R137") (pin "2") (pinfunction "2_2") (pintype "passive"))
      (node (ref "R141") (pin "1") (pinfunction "1_1") (pintype "passive"))
    )
    (net (code "32") (name "Net-(IC16-IN-)") (class "Default")
      (node (ref "IC16") (pin "2") (pinfunction "IN-_2") (pintype "input"))
      (node (ref "R136") (pin "1") (pinfunction "1_1") (pintype "passive"))
      (node (ref "R138") (pin "2") (pinfunction "2_2") (pintype "passive"))
      (node (ref "R140") (pin "1") (pinfunction "1_1") (pintype "passive"))
    )
    (net (code "33") (name "Net-(IC16-OUT)") (class "Default")
      (node (ref "C141") (pin "1") (pinfunction "1_1") (pintype "passive"))
      (node (ref "C143") (pin "1") (pinfunction "1_1") (pintype "passive"))
      (node (ref "IC16") (pin "6") (pinfunction "OUT_6") (pintype "output"))
      (node (ref "R135") (pin "2") (pinfunction "2_2") (pintype "passive"))
    )
    (net (code "34") (name "Net-(IC16-V+)") (class "Default")
      (node (ref "C142") (pin "2") (pinfunction "2_2") (pintype "passive"))
      (node (ref "IC16") (pin "7") (pinfunction "V+_7") (pintype "power_in"))
      (node (ref "L21") (pin "1") (pinfunction "1_1") (pintype "passive"))
      (node (ref "R137") (pin "1") (pinfunction "1_1") (pintype "passive"))
    )
    (net (code "35") (name "Net-(IC22-SET)") (class "Default")
      (node (ref "C472") (pin "1") (pinfunction "1_1") (pintype "passive"))
      (node (ref "IC22") (pin "7") (pinfunction "SET_7") (pintype "input"))
      (node (ref "R204") (pin "2") (pinfunction "2_2") (pintype "passive"))
    )
    (net (code "36") (name "Net-(IC23-SET)") (class "Default")
      (node (ref "C471") (pin "1") (pinfunction "1_1") (pintype "passive"))
      (node (ref "IC23") (pin "7") (pinfunction "SET_7") (pintype "input"))
      (node (ref "R208") (pin "2") (pinfunction "2_2") (pintype "passive"))
    )
    (net (code "37") (name "Net-(IC40-BIAS)") (class "Default")
      (node (ref "C87") (pin "1") (pinfunction "1_1") (pintype "passive"))
      (node (ref "IC40") (pin "40") (pinfunction "BIAS_40") (pintype "passive"))
    )
    (net (code "38") (name "Net-(IC40-CP)") (class "Default")
      (node (ref "IC40") (pin "4") (pinfunction "CP_4") (pintype "output"))
      (node (ref "R139") (pin "1") (pinfunction "1_1") (pintype "passive"))
      (node (ref "R142") (pin "1") (pinfunction "1_1") (pintype "passive"))
      (node (ref "TP57") (pin "1") (pinfunction "1_1") (pintype "bidirectional"))
    )
    (net (code "39") (name "Net-(IC40-DVDD3V)") (class "Default")
      (node (ref "C338") (pin "2") (pinfunction "2_2") (pintype "passive"))
      (node (ref "C91") (pin "2") (pinfunction "2_2") (pintype "passive"))
      (node (ref "IC40") (pin "16") (pinfunction "DVDD3V_16") (pintype "power_in"))
      (node (ref "R103") (pin "1") (pinfunction "1_1") (pintype "passive"))
    )
    (net (code "40") (name "Net-(IC40-RF_N)") (class "Default")
      (node (ref "C14") (pin "2") (pinfunction "2_2") (pintype "passive"))
      (node (ref "IC40") (pin "28") (pinfunction "RF_N_28") (pintype "output"))
    )
    (net (code "41") (name "Net-(IC40-RF_P)") (class "Default")
      (node (ref "C13") (pin "2") (pinfunction "2_2") (pintype "passive"))
      (node (ref "IC40") (pin "29") (pinfunction "RF_P_29") (pintype "output"))
    )
    (net (code "42") (name "Net-(IC40-XREFP)") (class "Default")
      (node (ref "C148") (pin "2") (pinfunction "2_2") (pintype "passive"))
      (node (ref "IC40") (pin "15") (pinfunction "XREFP_15") (pintype "input"))
      (node (ref "R97") (pin "2") (pinfunction "2_2") (pintype "passive"))
    )
    (net (code "43") (name "Net-(T14-D)") (class "Default")
      (node (ref "R75") (pin "1") (pinfunction "1_1") (pintype "passive"))
      (node (ref "T14") (pin "3") (pinfunction "D_3") (pintype "passive"))
    )
    (net (code "44") (name "Net-(T14-G)") (class "Default")
      (node (ref "R127") (pin "1") (pinfunction "1_1") (pintype "passive"))
      (node (ref "T14") (pin "1") (pinfunction "G_1") (pintype "passive"))
      (node (ref "T15") (pin "1") (pinfunction "G_1") (pintype "passive"))
      (node (ref "T16") (pin "3") (pinfunction "D_3") (pintype "passive"))
    )
    (net (code "45") (name "Net-(T15-D)") (class "Default")
      (node (ref "R76") (pin "1") (pinfunction "1_1") (pintype "passive"))
      (node (ref "T15") (pin "3") (pinfunction "D_3") (pintype "passive"))
    )
    (net (code "46") (name "P3V3_HMC") (class "Default")
      (node (ref "C335") (pin "2") (pinfunction "2_2") (pintype "passive"))
      (node (ref "C5") (pin "2") (pinfunction "2_2") (pintype "passive"))
      (node (ref "C87") (pin "2") (pinfunction "2_2") (pintype "passive"))
      (node (ref "C89") (pin "2") (pinfunction "2_2") (pintype "passive"))
      (node (ref "C90") (pin "2") (pinfunction "2_2") (pintype "passive"))
      (node (ref "C92") (pin "2") (pinfunction "2_2") (pintype "passive"))
      (node (ref "C93") (pin "2") (pinfunction "2_2") (pintype "passive"))
      (node (ref "C94") (pin "2") (pinfunction "2_2") (pintype "passive"))
      (node (ref "C95") (pin "2") (pinfunction "2_2") (pintype "passive"))
      (node (ref "IC23") (pin "10") (pinfunction "OUT_10") (pintype "output"))
      (node (ref "IC23") (pin "9") (pinfunction "OUTS_9") (pintype "output"))
      (node (ref "IC40") (pin "1") (pinfunction "AVDD_1") (pintype "power_in"))
      (node (ref "IC40") (pin "10") (pinfunction "RVDD_10") (pintype "power_in"))
      (node (ref "IC40") (pin "17") (pinfunction "CEN_17") (pintype "input"))
      (node (ref "IC40") (pin "18") (pinfunction "NC_18") (pintype "passive"))
      (node (ref "IC40") (pin "19") (pinfunction "NC_19") (pintype "passive"))
      (node (ref "IC40") (pin "20") (pinfunction "NC_20") (pintype "passive"))
      (node (ref "IC40") (pin "35") (pinfunction "VCCHF_35") (pintype "power_in"))
      (node (ref "IC40") (pin "36") (pinfunction "VCCPS_36") (pintype "power_in"))
      (node (ref "IC40") (pin "39") (pinfunction "VCCPD_39") (pintype "power_in"))
      (node (ref "R103") (pin "2") (pinfunction "2_2") (pintype "passive"))
      (node (ref "R76") (pin "2") (pinfunction "2_2") (pintype "passive"))
      (node (ref "TP75") (pin "1") (pinfunction "1_1") (pintype "bidirectional"))
    )
    (net (code "47") (name "P5V0_HMC") (class "Default")
      (node (ref "C2") (pin "2") (pinfunction "2_2") (pintype "passive"))
      (node (ref "IC22") (pin "10") (pinfunction "OUT_10") (pintype "output"))
      (node (ref "IC22") (pin "9") (pinfunction "OUTS_9") (pintype "output"))
      (node (ref "L21") (pin "2") (pinfunction "2_2") (pintype "passive"))
      (node (ref "L37") (pin "2") (pinfunction "2_2") (pintype "passive"))
      (node (ref "L39") (pin "2") (pinfunction "2_2") (pintype "passive"))
      (node (ref "R75") (pin "2") (pinfunction "2_2") (pintype "passive"))
      (node (ref "TP74") (pin "1") (pinfunction "1_1") (pintype "bidirectional"))
    )
    (net (code "48") (name "P6V0A") (class "Default")
      (node (ref "L13") (pin "1") (pinfunction "1_1") (pintype "passive"))
      (node (ref "R127") (pin "2") (pinfunction "2_2") (pintype "passive"))
    )
    (net (code "49") (name "unconnected-(IC22-PG-Pad4)") (class "Default")
      (node (ref "IC22") (pin "4") (pinfunction "PG_4") (pintype "output+no_connect"))
    )
    (net (code "50") (name "unconnected-(IC23-PG-Pad4)") (class "Default")
      (node (ref "IC23") (pin "4") (pinfunction "PG_4") (pintype "output+no_connect"))
    )
    (net (code "51") (name "unconnected-(IC40-NC-Pad2)") (class "Default")
      (node (ref "IC40") (pin "2") (pinfunction "NC_2") (pintype "passive+no_connect"))
    )
    (net (code "52") (name "unconnected-(IC40-NC-Pad8)") (class "Default")
      (node (ref "IC40") (pin "8") (pinfunction "NC_8") (pintype "passive+no_connect"))
    )
    (net (code "53") (name "unconnected-(IC40-NC-Pad9)") (class "Default")
      (node (ref "IC40") (pin "9") (pinfunction "NC_9") (pintype "passive+no_connect"))
    )
    (net (code "54") (name "unconnected-(IC40-NC-Pad11)") (class "Default")
      (node (ref "IC40") (pin "11") (pinfunction "NC_11") (pintype "passive+no_connect"))
    )
    (net (code "55") (name "unconnected-(IC40-NC-Pad12)") (class "Default")
      (node (ref "IC40") (pin "12") (pinfunction "NC_12") (pintype "passive+no_connect"))
    )
    (net (code "56") (name "unconnected-(IC40-NC-Pad13)") (class "Default")
      (node (ref "IC40") (pin "13") (pinfunction "NC_13") (pintype "passive+no_connect"))
    )
    (net (code "57") (name "unconnected-(IC40-NC-Pad14)") (class "Default")
      (node (ref "IC40") (pin "14") (pinfunction "NC_14") (pintype "passive+no_connect"))
    )
    (net (code "58") (name "unconnected-(IC40-NC-Pad34)") (class "Default")
      (node (ref "IC40") (pin "34") (pinfunction "NC_34") (pintype "passive+no_connect"))
    )
    (net (code "59") (name "unconnected-(IC40-NC-Pad37)") (class "Default")
      (node (ref "IC40") (pin "37") (pinfunction "NC_37") (pintype "passive+no_connect"))
    )
    (net (code "60") (name "unconnected-(IC40-NC-Pad38)") (class "Default")
      (node (ref "IC40") (pin "38") (pinfunction "NC_38") (pintype "passive+no_connect"))
    )
  )
)
